# Charging.net
KiCad netlist of a schematic drawn in EAGLE
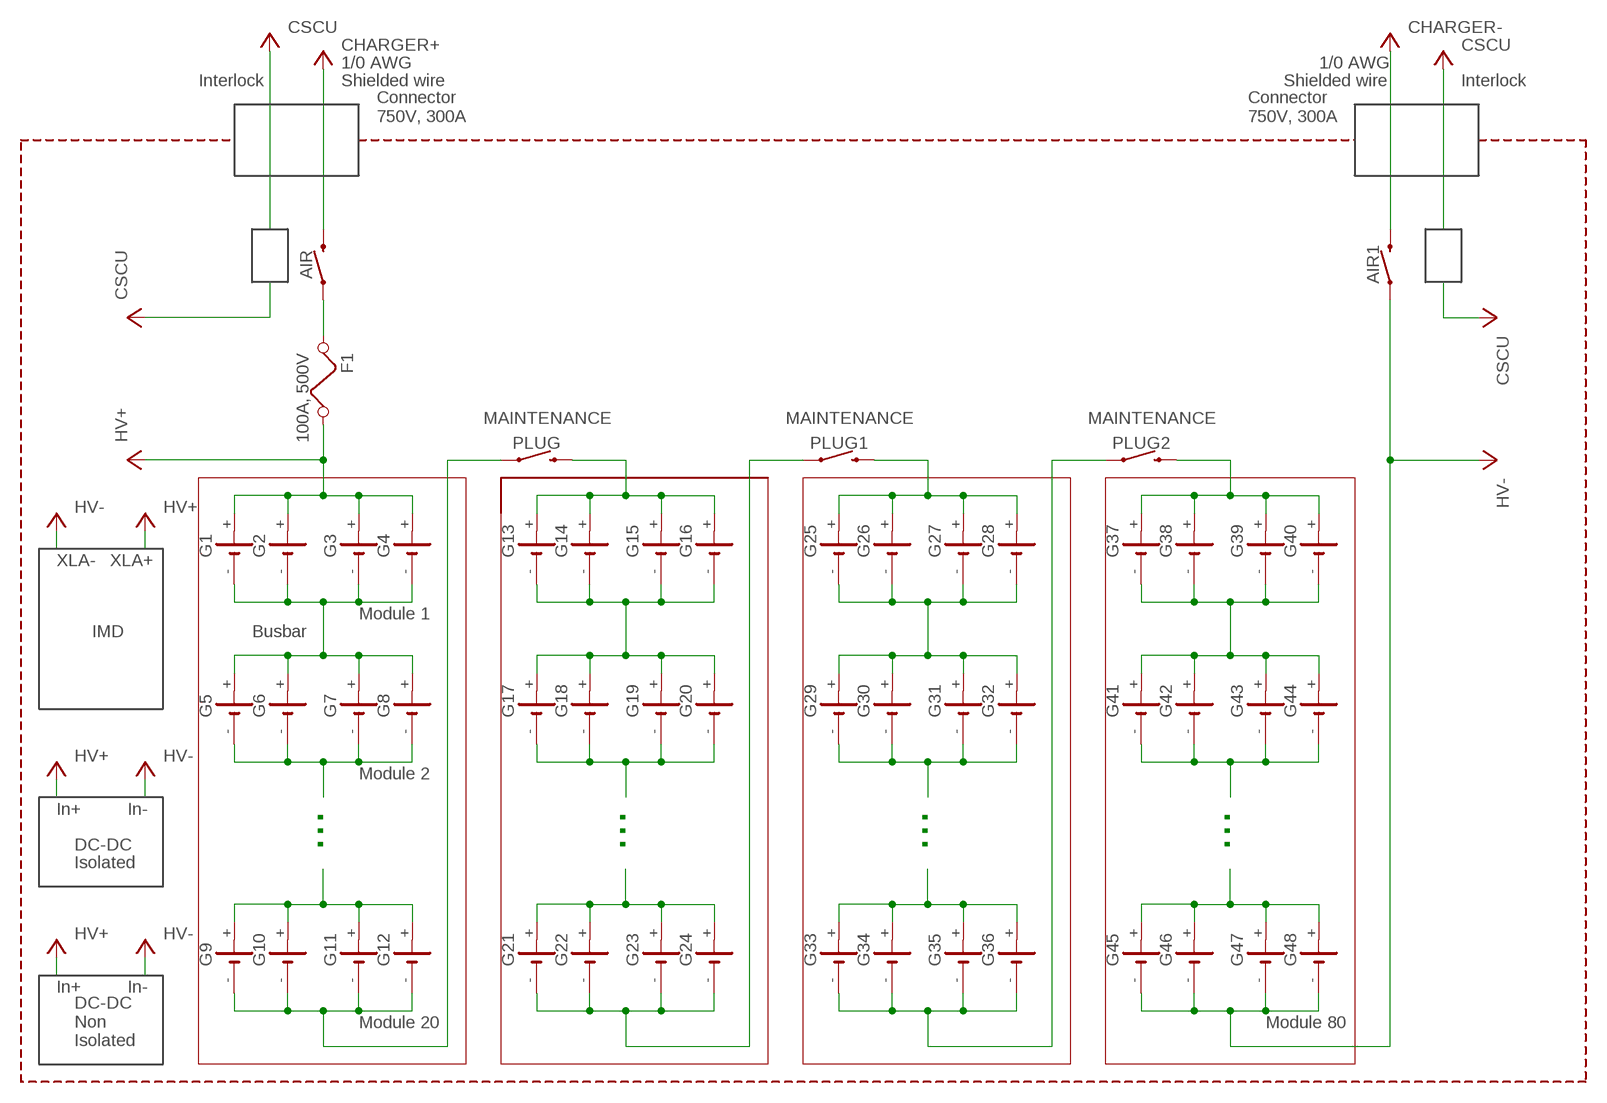
[diagram p0: schematic, sheet 1]

(export (version "E")
  (design (tool "Eeschema 10.0.6"))
  (components
    (comp (ref "AIR")
      (value "MOMENTARY-SWITCH-SPST-PTH-6.0MM")
      (footprint "eagle-import:TACTILE_SWITCH_PTH_6.0MM")
      (libsource (lib "eagle-import") (part "MOMENTARY-SWITCH-SPST-PTH-6.0MM"))
    )
    (comp (ref "AIR1")
      (value "MOMENTARY-SWITCH-SPST-PTH-6.0MM")
      (footprint "eagle-import:TACTILE_SWITCH_PTH_6.0MM")
      (libsource (lib "eagle-import") (part "MOMENTARY-SWITCH-SPST-PTH-6.0MM"))
    )
    (comp (ref "F1")
      (value "100A, 500V")
      (footprint "eagle-import:FUSE")
      (libsource (lib "eagle-import") (part "FUSE"))
    )
    (comp (ref "G1")
      (value "SL-160AA/PR")
      (footprint "eagle-import:SL-160AA_PR")
      (libsource (lib "eagle-import") (part "SL-160AA/PR"))
    )
    (comp (ref "G2")
      (value "SL-160AA/PR")
      (footprint "eagle-import:SL-160AA_PR")
      (libsource (lib "eagle-import") (part "SL-160AA/PR"))
    )
    (comp (ref "G3")
      (value "SL-160AA/PR")
      (footprint "eagle-import:SL-160AA_PR")
      (libsource (lib "eagle-import") (part "SL-160AA/PR"))
    )
    (comp (ref "G4")
      (value "SL-160AA/PR")
      (footprint "eagle-import:SL-160AA_PR")
      (libsource (lib "eagle-import") (part "SL-160AA/PR"))
    )
    (comp (ref "G5")
      (value "SL-160AA/PR")
      (footprint "eagle-import:SL-160AA_PR")
      (libsource (lib "eagle-import") (part "SL-160AA/PR"))
    )
    (comp (ref "G6")
      (value "SL-160AA/PR")
      (footprint "eagle-import:SL-160AA_PR")
      (libsource (lib "eagle-import") (part "SL-160AA/PR"))
    )
    (comp (ref "G7")
      (value "SL-160AA/PR")
      (footprint "eagle-import:SL-160AA_PR")
      (libsource (lib "eagle-import") (part "SL-160AA/PR"))
    )
    (comp (ref "G8")
      (value "SL-160AA/PR")
      (footprint "eagle-import:SL-160AA_PR")
      (libsource (lib "eagle-import") (part "SL-160AA/PR"))
    )
    (comp (ref "G9")
      (value "SL-160AA/PR")
      (footprint "eagle-import:SL-160AA_PR")
      (libsource (lib "eagle-import") (part "SL-160AA/PR"))
    )
    (comp (ref "G10")
      (value "SL-160AA/PR")
      (footprint "eagle-import:SL-160AA_PR")
      (libsource (lib "eagle-import") (part "SL-160AA/PR"))
    )
    (comp (ref "G11")
      (value "SL-160AA/PR")
      (footprint "eagle-import:SL-160AA_PR")
      (libsource (lib "eagle-import") (part "SL-160AA/PR"))
    )
    (comp (ref "G12")
      (value "SL-160AA/PR")
      (footprint "eagle-import:SL-160AA_PR")
      (libsource (lib "eagle-import") (part "SL-160AA/PR"))
    )
    (comp (ref "G13")
      (value "SL-160AA/PR")
      (footprint "eagle-import:SL-160AA_PR")
      (libsource (lib "eagle-import") (part "SL-160AA/PR"))
    )
    (comp (ref "G14")
      (value "SL-160AA/PR")
      (footprint "eagle-import:SL-160AA_PR")
      (libsource (lib "eagle-import") (part "SL-160AA/PR"))
    )
    (comp (ref "G15")
      (value "SL-160AA/PR")
      (footprint "eagle-import:SL-160AA_PR")
      (libsource (lib "eagle-import") (part "SL-160AA/PR"))
    )
    (comp (ref "G16")
      (value "SL-160AA/PR")
      (footprint "eagle-import:SL-160AA_PR")
      (libsource (lib "eagle-import") (part "SL-160AA/PR"))
    )
    (comp (ref "G17")
      (value "SL-160AA/PR")
      (footprint "eagle-import:SL-160AA_PR")
      (libsource (lib "eagle-import") (part "SL-160AA/PR"))
    )
    (comp (ref "G18")
      (value "SL-160AA/PR")
      (footprint "eagle-import:SL-160AA_PR")
      (libsource (lib "eagle-import") (part "SL-160AA/PR"))
    )
    (comp (ref "G19")
      (value "SL-160AA/PR")
      (footprint "eagle-import:SL-160AA_PR")
      (libsource (lib "eagle-import") (part "SL-160AA/PR"))
    )
    (comp (ref "G20")
      (value "SL-160AA/PR")
      (footprint "eagle-import:SL-160AA_PR")
      (libsource (lib "eagle-import") (part "SL-160AA/PR"))
    )
    (comp (ref "G21")
      (value "SL-160AA/PR")
      (footprint "eagle-import:SL-160AA_PR")
      (libsource (lib "eagle-import") (part "SL-160AA/PR"))
    )
    (comp (ref "G22")
      (value "SL-160AA/PR")
      (footprint "eagle-import:SL-160AA_PR")
      (libsource (lib "eagle-import") (part "SL-160AA/PR"))
    )
    (comp (ref "G23")
      (value "SL-160AA/PR")
      (footprint "eagle-import:SL-160AA_PR")
      (libsource (lib "eagle-import") (part "SL-160AA/PR"))
    )
    (comp (ref "G24")
      (value "SL-160AA/PR")
      (footprint "eagle-import:SL-160AA_PR")
      (libsource (lib "eagle-import") (part "SL-160AA/PR"))
    )
    (comp (ref "G25")
      (value "SL-160AA/PR")
      (footprint "eagle-import:SL-160AA_PR")
      (libsource (lib "eagle-import") (part "SL-160AA/PR"))
    )
    (comp (ref "G26")
      (value "SL-160AA/PR")
      (footprint "eagle-import:SL-160AA_PR")
      (libsource (lib "eagle-import") (part "SL-160AA/PR"))
    )
    (comp (ref "G27")
      (value "SL-160AA/PR")
      (footprint "eagle-import:SL-160AA_PR")
      (libsource (lib "eagle-import") (part "SL-160AA/PR"))
    )
    (comp (ref "G28")
      (value "SL-160AA/PR")
      (footprint "eagle-import:SL-160AA_PR")
      (libsource (lib "eagle-import") (part "SL-160AA/PR"))
    )
    (comp (ref "G29")
      (value "SL-160AA/PR")
      (footprint "eagle-import:SL-160AA_PR")
      (libsource (lib "eagle-import") (part "SL-160AA/PR"))
    )
    (comp (ref "G30")
      (value "SL-160AA/PR")
      (footprint "eagle-import:SL-160AA_PR")
      (libsource (lib "eagle-import") (part "SL-160AA/PR"))
    )
    (comp (ref "G31")
      (value "SL-160AA/PR")
      (footprint "eagle-import:SL-160AA_PR")
      (libsource (lib "eagle-import") (part "SL-160AA/PR"))
    )
    (comp (ref "G32")
      (value "SL-160AA/PR")
      (footprint "eagle-import:SL-160AA_PR")
      (libsource (lib "eagle-import") (part "SL-160AA/PR"))
    )
    (comp (ref "G33")
      (value "SL-160AA/PR")
      (footprint "eagle-import:SL-160AA_PR")
      (libsource (lib "eagle-import") (part "SL-160AA/PR"))
    )
    (comp (ref "G34")
      (value "SL-160AA/PR")
      (footprint "eagle-import:SL-160AA_PR")
      (libsource (lib "eagle-import") (part "SL-160AA/PR"))
    )
    (comp (ref "G35")
      (value "SL-160AA/PR")
      (footprint "eagle-import:SL-160AA_PR")
      (libsource (lib "eagle-import") (part "SL-160AA/PR"))
    )
    (comp (ref "G36")
      (value "SL-160AA/PR")
      (footprint "eagle-import:SL-160AA_PR")
      (libsource (lib "eagle-import") (part "SL-160AA/PR"))
    )
    (comp (ref "G37")
      (value "SL-160AA/PR")
      (footprint "eagle-import:SL-160AA_PR")
      (libsource (lib "eagle-import") (part "SL-160AA/PR"))
    )
    (comp (ref "G38")
      (value "SL-160AA/PR")
      (footprint "eagle-import:SL-160AA_PR")
      (libsource (lib "eagle-import") (part "SL-160AA/PR"))
    )
    (comp (ref "G39")
      (value "SL-160AA/PR")
      (footprint "eagle-import:SL-160AA_PR")
      (libsource (lib "eagle-import") (part "SL-160AA/PR"))
    )
    (comp (ref "G40")
      (value "SL-160AA/PR")
      (footprint "eagle-import:SL-160AA_PR")
      (libsource (lib "eagle-import") (part "SL-160AA/PR"))
    )
    (comp (ref "G41")
      (value "SL-160AA/PR")
      (footprint "eagle-import:SL-160AA_PR")
      (libsource (lib "eagle-import") (part "SL-160AA/PR"))
    )
    (comp (ref "G42")
      (value "SL-160AA/PR")
      (footprint "eagle-import:SL-160AA_PR")
      (libsource (lib "eagle-import") (part "SL-160AA/PR"))
    )
    (comp (ref "G43")
      (value "SL-160AA/PR")
      (footprint "eagle-import:SL-160AA_PR")
      (libsource (lib "eagle-import") (part "SL-160AA/PR"))
    )
    (comp (ref "G44")
      (value "SL-160AA/PR")
      (footprint "eagle-import:SL-160AA_PR")
      (libsource (lib "eagle-import") (part "SL-160AA/PR"))
    )
    (comp (ref "G45")
      (value "SL-160AA/PR")
      (footprint "eagle-import:SL-160AA_PR")
      (libsource (lib "eagle-import") (part "SL-160AA/PR"))
    )
    (comp (ref "G46")
      (value "SL-160AA/PR")
      (footprint "eagle-import:SL-160AA_PR")
      (libsource (lib "eagle-import") (part "SL-160AA/PR"))
    )
    (comp (ref "G47")
      (value "SL-160AA/PR")
      (footprint "eagle-import:SL-160AA_PR")
      (libsource (lib "eagle-import") (part "SL-160AA/PR"))
    )
    (comp (ref "G48")
      (value "SL-160AA/PR")
      (footprint "eagle-import:SL-160AA_PR")
      (libsource (lib "eagle-import") (part "SL-160AA/PR"))
    )
    (comp (ref "PLUG")
      (value "MOMENTARY-SWITCH-SPST-PTH-6.0MM")
      (footprint "eagle-import:TACTILE_SWITCH_PTH_6.0MM")
      (libsource (lib "eagle-import") (part "MOMENTARY-SWITCH-SPST-PTH-6.0MM"))
    )
    (comp (ref "PLUG1")
      (value "MOMENTARY-SWITCH-SPST-PTH-6.0MM")
      (footprint "eagle-import:TACTILE_SWITCH_PTH_6.0MM")
      (libsource (lib "eagle-import") (part "MOMENTARY-SWITCH-SPST-PTH-6.0MM"))
    )
    (comp (ref "PLUG2")
      (value "MOMENTARY-SWITCH-SPST-PTH-6.0MM")
      (footprint "eagle-import:TACTILE_SWITCH_PTH_6.0MM")
      (libsource (lib "eagle-import") (part "MOMENTARY-SWITCH-SPST-PTH-6.0MM"))
    )
  )
  (nets
    (net (code "1") (name "CHARGER+") (class "Default")
      (node (ref "AIR") (pin "3") (pinfunction "2_3") (pintype "passive"))
      (node (ref "AIR1") (pin "1") (pinfunction "1_1") (pintype "passive"))
      (node (ref "AIR1") (pin "3") (pinfunction "2_3") (pintype "passive"))
      (node (ref "F1") (pin "2") (pinfunction "2_2") (pintype "passive"))
      (node (ref "G1") (pin "+") (pinfunction "+_+") (pintype "passive"))
      (node (ref "G2") (pin "+") (pinfunction "+_+") (pintype "passive"))
      (node (ref "G3") (pin "+") (pinfunction "+_+") (pintype "passive"))
      (node (ref "G4") (pin "+") (pinfunction "+_+") (pintype "passive"))
      (node (ref "G45") (pin "-") (pinfunction "-_-") (pintype "passive"))
      (node (ref "G46") (pin "-") (pinfunction "-_-") (pintype "passive"))
      (node (ref "G47") (pin "-") (pinfunction "-_-") (pintype "passive"))
      (node (ref "G48") (pin "-") (pinfunction "-_-") (pintype "passive"))
    )
    (net (code "2") (name "Net-(AIR-Pad1)") (class "Default")
      (node (ref "AIR") (pin "1") (pinfunction "1_1") (pintype "passive"))
      (node (ref "F1") (pin "1") (pinfunction "1_1") (pintype "passive"))
    )
    (net (code "3") (name "Net-(G1-Pad-)") (class "Default")
      (node (ref "G1") (pin "-") (pinfunction "-_-") (pintype "passive"))
      (node (ref "G2") (pin "-") (pinfunction "-_-") (pintype "passive"))
      (node (ref "G3") (pin "-") (pinfunction "-_-") (pintype "passive"))
      (node (ref "G4") (pin "-") (pinfunction "-_-") (pintype "passive"))
      (node (ref "G5") (pin "+") (pinfunction "+_+") (pintype "passive"))
      (node (ref "G6") (pin "+") (pinfunction "+_+") (pintype "passive"))
      (node (ref "G7") (pin "+") (pinfunction "+_+") (pintype "passive"))
      (node (ref "G8") (pin "+") (pinfunction "+_+") (pintype "passive"))
    )
    (net (code "4") (name "Net-(G5-Pad-)") (class "Default")
      (node (ref "G5") (pin "-") (pinfunction "-_-") (pintype "passive"))
      (node (ref "G6") (pin "-") (pinfunction "-_-") (pintype "passive"))
      (node (ref "G7") (pin "-") (pinfunction "-_-") (pintype "passive"))
      (node (ref "G8") (pin "-") (pinfunction "-_-") (pintype "passive"))
    )
    (net (code "5") (name "Net-(G10-Pad+)") (class "Default")
      (node (ref "G10") (pin "+") (pinfunction "+_+") (pintype "passive"))
      (node (ref "G11") (pin "+") (pinfunction "+_+") (pintype "passive"))
      (node (ref "G12") (pin "+") (pinfunction "+_+") (pintype "passive"))
      (node (ref "G9") (pin "+") (pinfunction "+_+") (pintype "passive"))
    )
    (net (code "6") (name "Net-(G10-Pad-)") (class "Default")
      (node (ref "G10") (pin "-") (pinfunction "-_-") (pintype "passive"))
      (node (ref "G11") (pin "-") (pinfunction "-_-") (pintype "passive"))
      (node (ref "G12") (pin "-") (pinfunction "-_-") (pintype "passive"))
      (node (ref "G9") (pin "-") (pinfunction "-_-") (pintype "passive"))
      (node (ref "PLUG") (pin "1") (pinfunction "1_1") (pintype "passive"))
    )
    (net (code "7") (name "Net-(G13-Pad-)") (class "Default")
      (node (ref "G13") (pin "-") (pinfunction "-_-") (pintype "passive"))
      (node (ref "G14") (pin "-") (pinfunction "-_-") (pintype "passive"))
      (node (ref "G15") (pin "-") (pinfunction "-_-") (pintype "passive"))
      (node (ref "G16") (pin "-") (pinfunction "-_-") (pintype "passive"))
      (node (ref "G17") (pin "+") (pinfunction "+_+") (pintype "passive"))
      (node (ref "G18") (pin "+") (pinfunction "+_+") (pintype "passive"))
      (node (ref "G19") (pin "+") (pinfunction "+_+") (pintype "passive"))
      (node (ref "G20") (pin "+") (pinfunction "+_+") (pintype "passive"))
    )
    (net (code "8") (name "Net-(G17-Pad-)") (class "Default")
      (node (ref "G17") (pin "-") (pinfunction "-_-") (pintype "passive"))
      (node (ref "G18") (pin "-") (pinfunction "-_-") (pintype "passive"))
      (node (ref "G19") (pin "-") (pinfunction "-_-") (pintype "passive"))
      (node (ref "G20") (pin "-") (pinfunction "-_-") (pintype "passive"))
    )
    (net (code "9") (name "Net-(G21-Pad+)") (class "Default")
      (node (ref "G21") (pin "+") (pinfunction "+_+") (pintype "passive"))
      (node (ref "G22") (pin "+") (pinfunction "+_+") (pintype "passive"))
      (node (ref "G23") (pin "+") (pinfunction "+_+") (pintype "passive"))
      (node (ref "G24") (pin "+") (pinfunction "+_+") (pintype "passive"))
    )
    (net (code "10") (name "Net-(G21-Pad-)") (class "Default")
      (node (ref "G21") (pin "-") (pinfunction "-_-") (pintype "passive"))
      (node (ref "G22") (pin "-") (pinfunction "-_-") (pintype "passive"))
      (node (ref "G23") (pin "-") (pinfunction "-_-") (pintype "passive"))
      (node (ref "G24") (pin "-") (pinfunction "-_-") (pintype "passive"))
      (node (ref "PLUG1") (pin "1") (pinfunction "1_1") (pintype "passive"))
    )
    (net (code "11") (name "Net-(G25-Pad-)") (class "Default")
      (node (ref "G25") (pin "-") (pinfunction "-_-") (pintype "passive"))
      (node (ref "G26") (pin "-") (pinfunction "-_-") (pintype "passive"))
      (node (ref "G27") (pin "-") (pinfunction "-_-") (pintype "passive"))
      (node (ref "G28") (pin "-") (pinfunction "-_-") (pintype "passive"))
      (node (ref "G29") (pin "+") (pinfunction "+_+") (pintype "passive"))
      (node (ref "G30") (pin "+") (pinfunction "+_+") (pintype "passive"))
      (node (ref "G31") (pin "+") (pinfunction "+_+") (pintype "passive"))
      (node (ref "G32") (pin "+") (pinfunction "+_+") (pintype "passive"))
    )
    (net (code "12") (name "Net-(G29-Pad-)") (class "Default")
      (node (ref "G29") (pin "-") (pinfunction "-_-") (pintype "passive"))
      (node (ref "G30") (pin "-") (pinfunction "-_-") (pintype "passive"))
      (node (ref "G31") (pin "-") (pinfunction "-_-") (pintype "passive"))
      (node (ref "G32") (pin "-") (pinfunction "-_-") (pintype "passive"))
    )
    (net (code "13") (name "Net-(G33-Pad+)") (class "Default")
      (node (ref "G33") (pin "+") (pinfunction "+_+") (pintype "passive"))
      (node (ref "G34") (pin "+") (pinfunction "+_+") (pintype "passive"))
      (node (ref "G35") (pin "+") (pinfunction "+_+") (pintype "passive"))
      (node (ref "G36") (pin "+") (pinfunction "+_+") (pintype "passive"))
    )
    (net (code "14") (name "Net-(G33-Pad-)") (class "Default")
      (node (ref "G33") (pin "-") (pinfunction "-_-") (pintype "passive"))
      (node (ref "G34") (pin "-") (pinfunction "-_-") (pintype "passive"))
      (node (ref "G35") (pin "-") (pinfunction "-_-") (pintype "passive"))
      (node (ref "G36") (pin "-") (pinfunction "-_-") (pintype "passive"))
      (node (ref "PLUG2") (pin "1") (pinfunction "1_1") (pintype "passive"))
    )
    (net (code "15") (name "Net-(G37-Pad-)") (class "Default")
      (node (ref "G37") (pin "-") (pinfunction "-_-") (pintype "passive"))
      (node (ref "G38") (pin "-") (pinfunction "-_-") (pintype "passive"))
      (node (ref "G39") (pin "-") (pinfunction "-_-") (pintype "passive"))
      (node (ref "G40") (pin "-") (pinfunction "-_-") (pintype "passive"))
      (node (ref "G41") (pin "+") (pinfunction "+_+") (pintype "passive"))
      (node (ref "G42") (pin "+") (pinfunction "+_+") (pintype "passive"))
      (node (ref "G43") (pin "+") (pinfunction "+_+") (pintype "passive"))
      (node (ref "G44") (pin "+") (pinfunction "+_+") (pintype "passive"))
    )
    (net (code "16") (name "Net-(G41-Pad-)") (class "Default")
      (node (ref "G41") (pin "-") (pinfunction "-_-") (pintype "passive"))
      (node (ref "G42") (pin "-") (pinfunction "-_-") (pintype "passive"))
      (node (ref "G43") (pin "-") (pinfunction "-_-") (pintype "passive"))
      (node (ref "G44") (pin "-") (pinfunction "-_-") (pintype "passive"))
    )
    (net (code "17") (name "Net-(G45-Pad+)") (class "Default")
      (node (ref "G45") (pin "+") (pinfunction "+_+") (pintype "passive"))
      (node (ref "G46") (pin "+") (pinfunction "+_+") (pintype "passive"))
      (node (ref "G47") (pin "+") (pinfunction "+_+") (pintype "passive"))
      (node (ref "G48") (pin "+") (pinfunction "+_+") (pintype "passive"))
    )
    (net (code "18") (name "Net-(PLUG-2)") (class "Default")
      (node (ref "G13") (pin "+") (pinfunction "+_+") (pintype "passive"))
      (node (ref "G14") (pin "+") (pinfunction "+_+") (pintype "passive"))
      (node (ref "G15") (pin "+") (pinfunction "+_+") (pintype "passive"))
      (node (ref "G16") (pin "+") (pinfunction "+_+") (pintype "passive"))
      (node (ref "PLUG") (pin "3") (pinfunction "2_3") (pintype "passive"))
    )
    (net (code "19") (name "Net-(PLUG1-2)") (class "Default")
      (node (ref "G25") (pin "+") (pinfunction "+_+") (pintype "passive"))
      (node (ref "G26") (pin "+") (pinfunction "+_+") (pintype "passive"))
      (node (ref "G27") (pin "+") (pinfunction "+_+") (pintype "passive"))
      (node (ref "G28") (pin "+") (pinfunction "+_+") (pintype "passive"))
      (node (ref "PLUG1") (pin "3") (pinfunction "2_3") (pintype "passive"))
    )
    (net (code "20") (name "Net-(PLUG2-2)") (class "Default")
      (node (ref "G37") (pin "+") (pinfunction "+_+") (pintype "passive"))
      (node (ref "G38") (pin "+") (pinfunction "+_+") (pintype "passive"))
      (node (ref "G39") (pin "+") (pinfunction "+_+") (pintype "passive"))
      (node (ref "G40") (pin "+") (pinfunction "+_+") (pintype "passive"))
      (node (ref "PLUG2") (pin "3") (pinfunction "2_3") (pintype "passive"))
    )
  )
)
